# Power_PMIC.net
KiCad netlist of a schematic drawn in Altium Designer
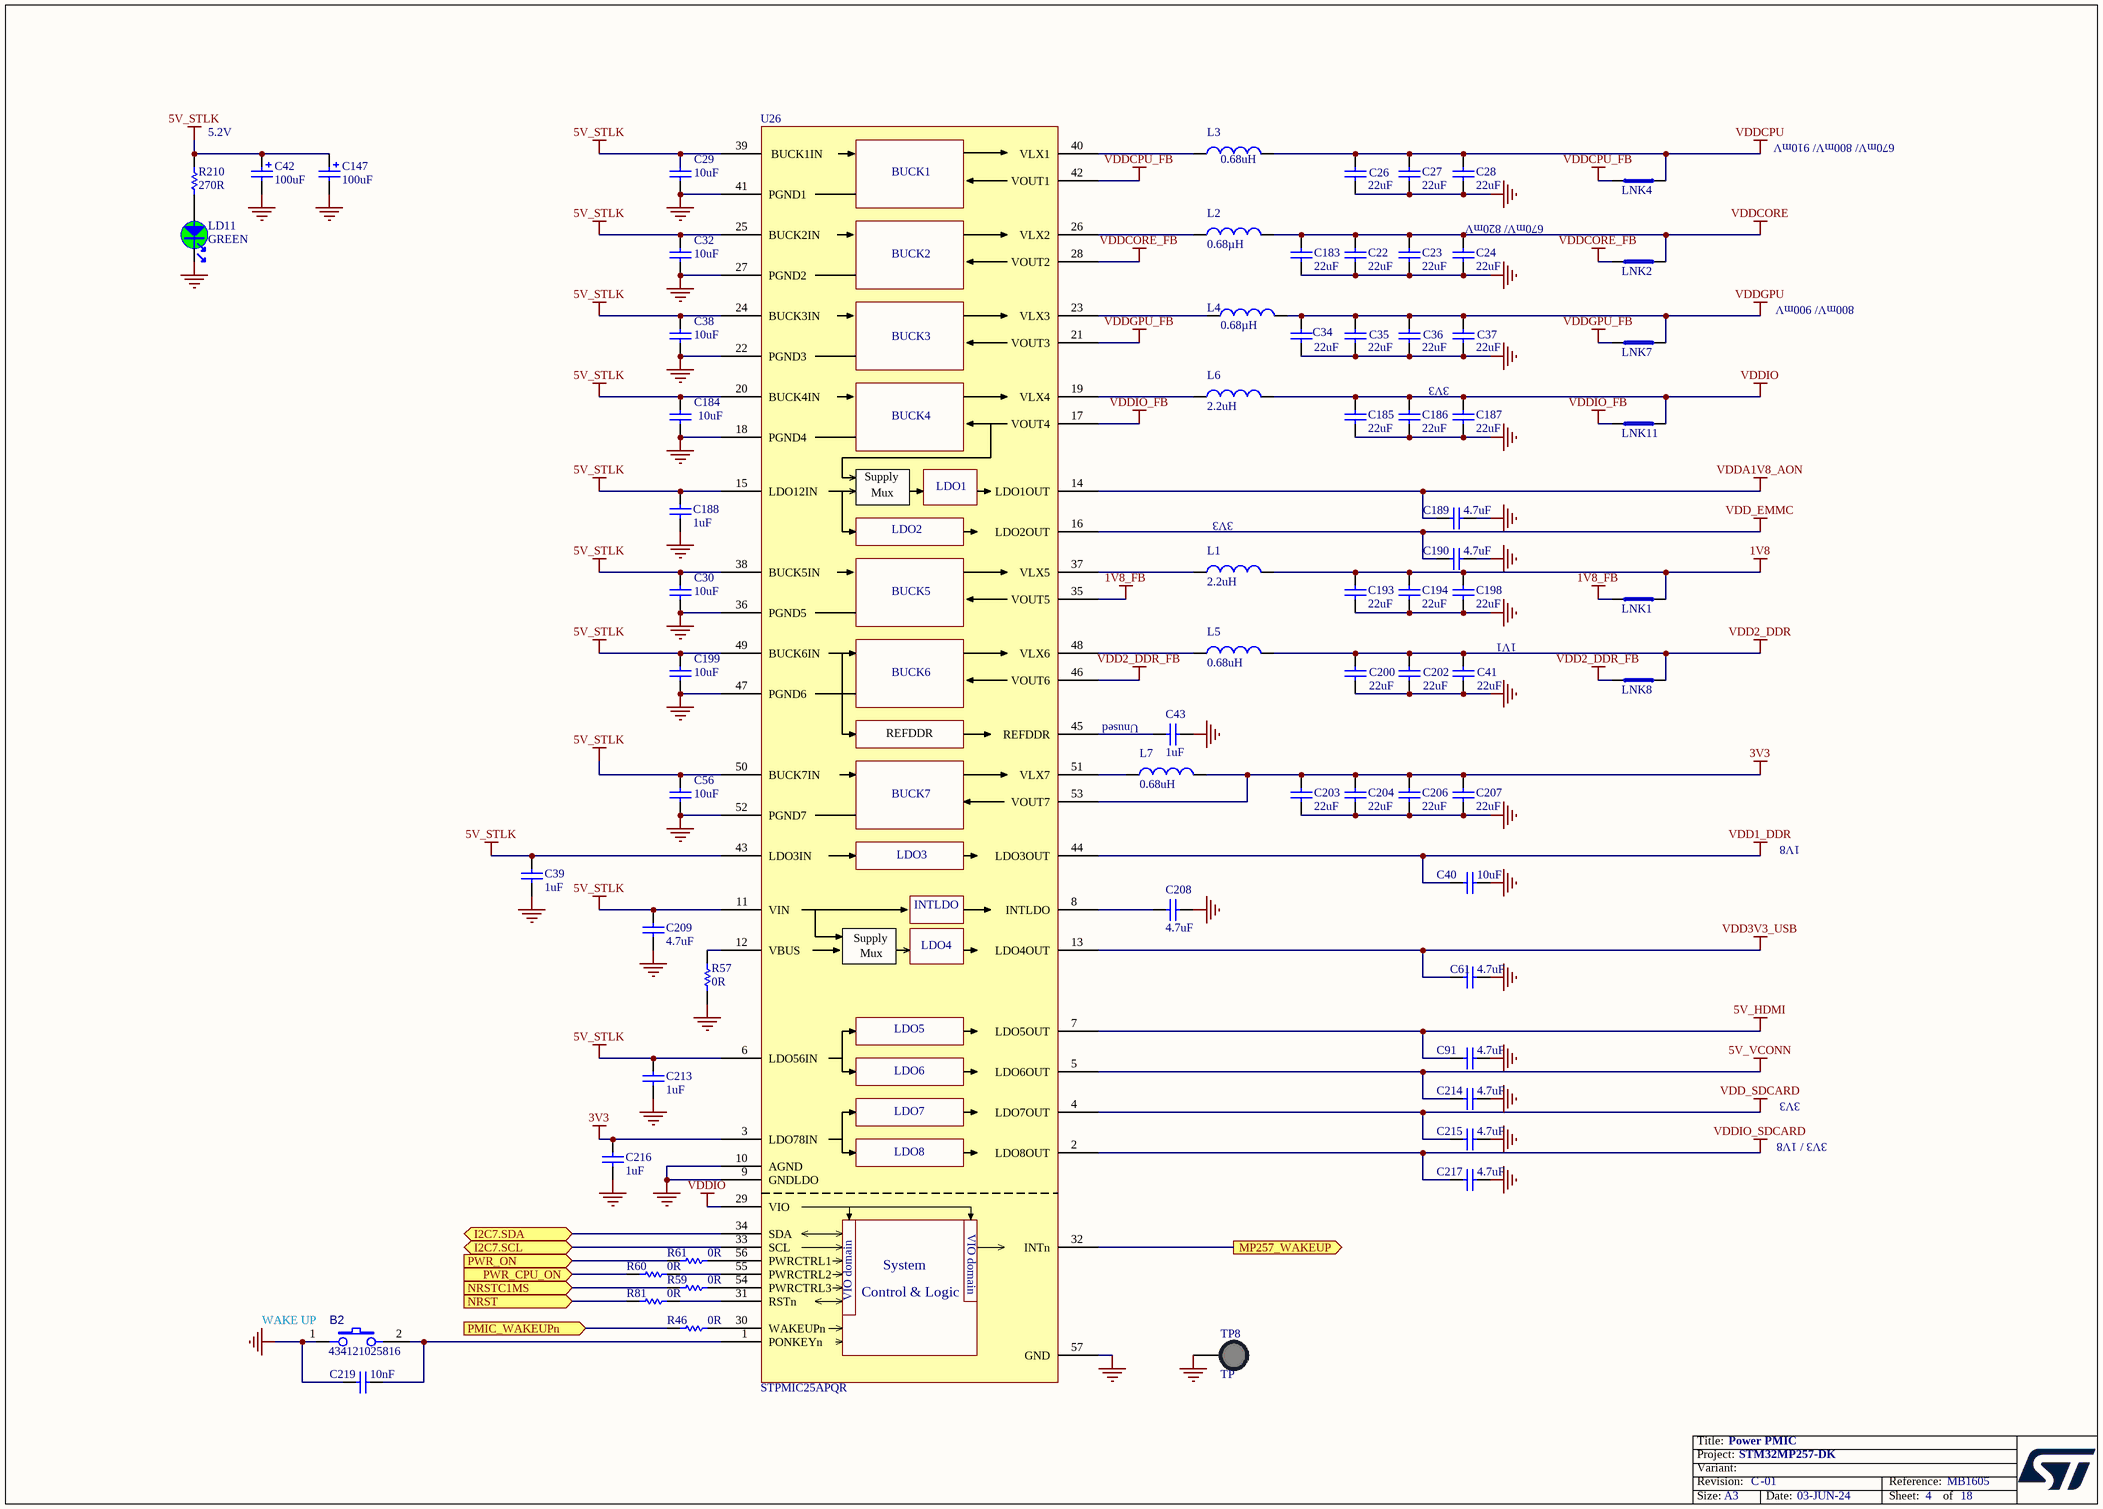
[diagram p0: Power_PMIC.SchDoc]

(export (version "E")
  (design (tool "Eeschema 10.0.6"))
  (components
    (comp (ref "B2")
      (value "434121025816")
      (footprint "SWI_WE_434121025816")
      (description "Switch tactile, SPST-NO, 50mA, 12V, 6x3.8mm")
      (fields
        (field (name "INTERNAL_PART_NUMBER") "MCD-03492")
        (field (name "MANUFACTURER") "WURTH ELEKTRONIC")
      )
      (libsource (lib "MCD_PARTS_database") (part "SW_PUSH_SMD_2P"))
    )
    (comp (ref "C22")
      (value "22uF")
      (footprint "C0603")
      (description "Capacitor, MLCC, 22uF, 6V3, X5R, +/-20%, 0603, T=0,8mm")
      (fields
        (field (name "INTERNAL_PART_NUMBER") "MCD-00100")
        (field (name "MANUFACTURER_PART_NUMBER") "GRM188R60J226MEA0J")
      )
      (libsource (lib "MCD_PARTS_database") (part "Capacitor"))
    )
    (comp (ref "C23")
      (value "22uF")
      (footprint "C0603")
      (description "Capacitor, MLCC, 22uF, 6V3, X5R, +/-20%, 0603, T=0,8mm")
      (fields
        (field (name "INTERNAL_PART_NUMBER") "MCD-00100")
        (field (name "MANUFACTURER_PART_NUMBER") "GRM188R60J226MEA0J")
      )
      (libsource (lib "MCD_PARTS_database") (part "Capacitor"))
    )
    (comp (ref "C24")
      (value "22uF")
      (footprint "C0603")
      (description "Capacitor, MLCC, 22uF, 6V3, X5R, +/-20%, 0603, T=0,8mm")
      (fields
        (field (name "INTERNAL_PART_NUMBER") "MCD-00100")
        (field (name "MANUFACTURER_PART_NUMBER") "GRM188R60J226MEA0J")
      )
      (libsource (lib "MCD_PARTS_database") (part "Capacitor"))
    )
    (comp (ref "C26")
      (value "22uF")
      (footprint "C0603")
      (description "Capacitor, MLCC, 22uF, 6V3, X5R, +/-20%, 0603, T=0,8mm")
      (fields
        (field (name "INTERNAL_PART_NUMBER") "MCD-00100")
        (field (name "MANUFACTURER_PART_NUMBER") "GRM188R60J226MEA0J")
      )
      (libsource (lib "MCD_PARTS_database") (part "Capacitor"))
    )
    (comp (ref "C27")
      (value "22uF")
      (footprint "C0603")
      (description "Capacitor, MLCC, 22uF, 6V3, X5R, +/-20%, 0603, T=0,8mm")
      (fields (field (name "INTERNAL_PART_NUMBER") "MCD-00100") (field (name "MANUFACTURER") "MURATA"))
      (libsource (lib "MCD_PARTS_database") (part "Capacitor"))
    )
    (comp (ref "C28")
      (value "22uF")
      (footprint "C0603")
      (description "Capacitor, MLCC, 22uF, 6V3, X5R, +/-20%, 0603, T=0,8mm")
      (fields (field (name "INTERNAL_PART_NUMBER") "MCD-00100") (field (name "MANUFACTURER") "MURATA"))
      (libsource (lib "MCD_PARTS_database") (part "Capacitor"))
    )
    (comp (ref "C29")
      (value "10uF")
      (footprint "C0603")
      (description "Capacitor, MLCC, 10uF, 10V, X5R, +/-10%, 0603, T=0,8mm")
      (fields
        (field (name "INTERNAL_PART_NUMBER") "MCD-00099")
        (field (name "MANUFACTURER_PART_NUMBER") "GRM188R61A106KE69D")
      )
      (libsource (lib "MCD_PARTS_database") (part "Capacitor"))
    )
    (comp (ref "C30")
      (value "10uF")
      (footprint "C0603")
      (description "Capacitor, MLCC, 10uF, 10V, X5R, +/-10%, 0603, T=0,8mm")
      (fields
        (field (name "INTERNAL_PART_NUMBER") "MCD-00099")
        (field (name "MANUFACTURER_PART_NUMBER") "GRM188R61A106KE69D")
      )
      (libsource (lib "MCD_PARTS_database") (part "Capacitor"))
    )
    (comp (ref "C32")
      (value "10uF")
      (footprint "C0603")
      (description "Capacitor, MLCC, 10uF, 10V, X5R, +/-10%, 0603, T=0,8mm")
      (fields
        (field (name "INTERNAL_PART_NUMBER") "MCD-00099")
        (field (name "MANUFACTURER_PART_NUMBER") "GRM188R61A106KE69D")
      )
      (libsource (lib "MCD_PARTS_database") (part "Capacitor"))
    )
    (comp (ref "C34")
      (value "22uF")
      (footprint "C0603")
      (description "Capacitor, MLCC, 22uF, 6V3, X5R, +/-20%, 0603, T=0,8mm")
      (fields
        (field (name "INTERNAL_PART_NUMBER") "MCD-00100")
        (field (name "MANUFACTURER_PART_NUMBER") "GRM188R60J226MEA0J")
      )
      (libsource (lib "MCD_PARTS_database") (part "Capacitor"))
    )
    (comp (ref "C35")
      (value "22uF")
      (footprint "C0603")
      (description "Capacitor, MLCC, 22uF, 6V3, X5R, +/-20%, 0603, T=0,8mm")
      (fields
        (field (name "INTERNAL_PART_NUMBER") "MCD-00100")
        (field (name "MANUFACTURER_PART_NUMBER") "GRM188R60J226MEA0J")
      )
      (libsource (lib "MCD_PARTS_database") (part "Capacitor"))
    )
    (comp (ref "C36")
      (value "22uF")
      (footprint "C0603")
      (description "Capacitor, MLCC, 22uF, 6V3, X5R, +/-20%, 0603, T=0,8mm")
      (fields
        (field (name "INTERNAL_PART_NUMBER") "MCD-00100")
        (field (name "MANUFACTURER_PART_NUMBER") "GRM188R60J226MEA0J")
      )
      (libsource (lib "MCD_PARTS_database") (part "Capacitor"))
    )
    (comp (ref "C37")
      (value "22uF")
      (footprint "C0603")
      (description "Capacitor, MLCC, 22uF, 6V3, X5R, +/-20%, 0603, T=0,8mm")
      (fields
        (field (name "INTERNAL_PART_NUMBER") "MCD-00100")
        (field (name "MANUFACTURER_PART_NUMBER") "GRM188R60J226MEA0J")
      )
      (libsource (lib "MCD_PARTS_database") (part "Capacitor"))
    )
    (comp (ref "C38")
      (value "10uF")
      (footprint "C0603")
      (description "Capacitor, MLCC, 10uF, 10V, X5R, +/-10%, 0603, T=0,8mm")
      (fields
        (field (name "INTERNAL_PART_NUMBER") "MCD-00099")
        (field (name "MANUFACTURER_PART_NUMBER") "GRM188R61A106KE69D")
      )
      (libsource (lib "MCD_PARTS_database") (part "Capacitor"))
    )
    (comp (ref "C39")
      (value "1uF")
      (footprint "C0402")
      (description "Capacitor, MLCC, 1uF, 25V, X5R, +/-10%, 0402, T=0.5mm")
      (fields (field (name "INTERNAL_PART_NUMBER") "MCD-00095") (field (name "MANUFACTURER") "MURATA"))
      (libsource (lib "MCD_PARTS_database") (part "Capacitor"))
    )
    (comp (ref "C40")
      (value "10uF")
      (footprint "C0402")
      (description "Capacitor, MLCC, 10uF, 6.3V, X5R, +/-20%, 0402, T=0.5mm")
      (fields (field (name "INTERNAL_PART_NUMBER") "MCD-03140") (field (name "MANUFACTURER") "MURATA"))
      (libsource (lib "MCD_PARTS_database") (part "Capacitor"))
    )
    (comp (ref "C41")
      (value "22uF")
      (footprint "C0603")
      (description "Capacitor, MLCC, 22uF, 6V3, X5R, +/-20%, 0603, T=0,8mm")
      (fields
        (field (name "INTERNAL_PART_NUMBER") "MCD-00100")
        (field (name "MANUFACTURER_PART_NUMBER") "GRM188R60J226MEA0J")
      )
      (libsource (lib "MCD_PARTS_database") (part "Capacitor"))
    )
    (comp (ref "C42")
      (value "100uF")
      (footprint "CPOL_TCJ-B_1210_H210")
      (description "Capacitor, Tantalum, 100uF, 6V3, 40mR, +/-20%,  Type_B (3528 metric), T=1.9mm")
      (fields (field (name "INTERNAL_PART_NUMBER") "MCD-01796") (field (name "MANUFACTURER") "AVX"))
      (libsource (lib "MCD_PARTS_database") (part "Cap_POL_TANA"))
    )
    (comp (ref "C43")
      (value "1uF")
      (footprint "C0402")
      (description "Capacitor, MLCC, 1uF, 25V, X5R, +/-10%, 0402, T=0.5mm")
      (fields (field (name "INTERNAL_PART_NUMBER") "MCD-00095") (field (name "MANUFACTURER") "MURATA"))
      (libsource (lib "MCD_PARTS_database") (part "Capacitor"))
    )
    (comp (ref "C56")
      (value "10uF")
      (footprint "C0603")
      (description "Capacitor, MLCC, 10uF, 10V, X5R, +/-10%, 0603, T=0,8mm")
      (fields
        (field (name "INTERNAL_PART_NUMBER") "MCD-00099")
        (field (name "MANUFACTURER_PART_NUMBER") "GRM188R61A106KE69D")
      )
      (libsource (lib "MCD_PARTS_database") (part "Capacitor"))
    )
    (comp (ref "C61")
      (value "4.7uF")
      (footprint "C0402")
      (description "Capacitor, MLCC, 4.7uF, 6V3, X5R, +/-20%, 0402, T=0.5mm")
      (fields
        (field (name "INTERNAL_PART_NUMBER") "MCD-01356")
        (field (name "MANUFACTURER_PART_NUMBER") "GRM155R60J475ME47")
      )
      (libsource (lib "MCD_PARTS_database") (part "Capacitor"))
    )
    (comp (ref "C91")
      (value "4.7uF")
      (footprint "C0402")
      (description "Capacitor, MLCC, 4.7uF, 6V3, X5R, +/-20%, 0402, T=0.5mm")
      (fields
        (field (name "INTERNAL_PART_NUMBER") "MCD-01356")
        (field (name "MANUFACTURER_PART_NUMBER") "GRM155R60J475ME47")
      )
      (libsource (lib "MCD_PARTS_database") (part "Capacitor"))
    )
    (comp (ref "C147")
      (value "100uF")
      (footprint "CPOL_TCJ-B_1210_H210")
      (description "Capacitor, Tantalum, 100uF, 6V3, 40mR, +/-20%,  Type_B (3528 metric), T=1.9mm")
      (fields (field (name "INTERNAL_PART_NUMBER") "MCD-01796") (field (name "MANUFACTURER") "AVX"))
      (libsource (lib "MCD_PARTS_database") (part "Cap_POL_TANA"))
    )
    (comp (ref "C183")
      (value "22uF")
      (footprint "C0603")
      (description "Capacitor, MLCC, 22uF, 6V3, X5R, +/-20%, 0603, T=0,8mm")
      (fields (field (name "INTERNAL_PART_NUMBER") "MCD-00100") (field (name "MANUFACTURER") "MURATA"))
      (libsource (lib "MCD_PARTS_database") (part "Capacitor"))
    )
    (comp (ref "C184")
      (value "10uF")
      (footprint "C0603")
      (description "Capacitor, MLCC, 10uF, 10V, X5R, +/-10%, 0603, T=0,8mm")
      (fields
        (field (name "INTERNAL_PART_NUMBER") "MCD-00099")
        (field (name "MANUFACTURER_PART_NUMBER") "GRM188R61A106KE69D")
      )
      (libsource (lib "MCD_PARTS_database") (part "Capacitor"))
    )
    (comp (ref "C185")
      (value "22uF")
      (footprint "C0805")
      (description "Capacitor, MLCC, 22uF, 10V, X5R, +/-20%, 0805, T=1,25mm")
      (fields (field (name "INTERNAL_PART_NUMBER") "MCD-03139") (field (name "MANUFACTURER") "MURATA"))
      (libsource (lib "MCD_PARTS_database") (part "Capacitor"))
    )
    (comp (ref "C186")
      (value "22uF")
      (footprint "C0805")
      (description "Capacitor, MLCC, 22uF, 10V, X5R, +/-20%, 0805, T=1,25mm")
      (fields (field (name "INTERNAL_PART_NUMBER") "MCD-03139") (field (name "MANUFACTURER") "MURATA"))
      (libsource (lib "MCD_PARTS_database") (part "Capacitor"))
    )
    (comp (ref "C187")
      (value "22uF")
      (footprint "C0805")
      (description "Capacitor, MLCC, 22uF, 10V, X5R, +/-20%, 0805, T=1,25mm")
      (fields (field (name "INTERNAL_PART_NUMBER") "MCD-03139") (field (name "MANUFACTURER") "MURATA"))
      (libsource (lib "MCD_PARTS_database") (part "Capacitor"))
    )
    (comp (ref "C188")
      (value "1uF")
      (footprint "C0402")
      (description "Capacitor, MLCC, 1uF, 25V, X5R, +/-10%, 0402, T=0.5mm")
      (fields (field (name "INTERNAL_PART_NUMBER") "MCD-00095") (field (name "MANUFACTURER") "MURATA"))
      (libsource (lib "MCD_PARTS_database") (part "Capacitor"))
    )
    (comp (ref "C189")
      (value "4.7uF")
      (footprint "C0402")
      (description "Capacitor, MLCC, 4.7uF, 6V3, X5R, +/-20%, 0402, T=0.5mm")
      (fields
        (field (name "INTERNAL_PART_NUMBER") "MCD-01356")
        (field (name "MANUFACTURER_PART_NUMBER") "GRM155R60J475ME47")
      )
      (libsource (lib "MCD_PARTS_database") (part "Capacitor"))
    )
    (comp (ref "C190")
      (value "4.7uF")
      (footprint "C0402")
      (description "Capacitor, MLCC, 4.7uF, 6V3, X5R, +/-20%, 0402, T=0.5mm")
      (fields
        (field (name "INTERNAL_PART_NUMBER") "MCD-01356")
        (field (name "MANUFACTURER_PART_NUMBER") "GRM155R60J475ME47")
      )
      (libsource (lib "MCD_PARTS_database") (part "Capacitor"))
    )
    (comp (ref "C193")
      (value "22uF")
      (footprint "C0805")
      (description "Capacitor, MLCC, 22uF, 10V, X5R, +/-20%, 0805, T=1,25mm")
      (fields (field (name "INTERNAL_PART_NUMBER") "MCD-03139") (field (name "MANUFACTURER") "MURATA"))
      (libsource (lib "MCD_PARTS_database") (part "Capacitor"))
    )
    (comp (ref "C194")
      (value "22uF")
      (footprint "C0805")
      (description "Capacitor, MLCC, 22uF, 10V, X5R, +/-20%, 0805, T=1,25mm")
      (fields (field (name "INTERNAL_PART_NUMBER") "MCD-03139") (field (name "MANUFACTURER") "MURATA"))
      (libsource (lib "MCD_PARTS_database") (part "Capacitor"))
    )
    (comp (ref "C198")
      (value "22uF")
      (footprint "C0805")
      (description "Capacitor, MLCC, 22uF, 10V, X5R, +/-20%, 0805, T=1,25mm")
      (fields (field (name "INTERNAL_PART_NUMBER") "MCD-03139") (field (name "MANUFACTURER") "MURATA"))
      (libsource (lib "MCD_PARTS_database") (part "Capacitor"))
    )
    (comp (ref "C199")
      (value "10uF")
      (footprint "C0603")
      (description "Capacitor, MLCC, 10uF, 10V, X5R, +/-10%, 0603, T=0,8mm")
      (fields
        (field (name "INTERNAL_PART_NUMBER") "MCD-00099")
        (field (name "MANUFACTURER_PART_NUMBER") "GRM188R61A106KE69D")
      )
      (libsource (lib "MCD_PARTS_database") (part "Capacitor"))
    )
    (comp (ref "C200")
      (value "22uF")
      (footprint "C0603")
      (description "Capacitor, MLCC, 22uF, 6V3, X5R, +/-20%, 0603, T=0,8mm")
      (fields
        (field (name "INTERNAL_PART_NUMBER") "MCD-00100")
        (field (name "MANUFACTURER_PART_NUMBER") "GRM188R60J226MEA0J")
      )
      (libsource (lib "MCD_PARTS_database") (part "Capacitor"))
    )
    (comp (ref "C202")
      (value "22uF")
      (footprint "C0603")
      (description "Capacitor, MLCC, 22uF, 6V3, X5R, +/-20%, 0603, T=0,8mm")
      (fields
        (field (name "INTERNAL_PART_NUMBER") "MCD-00100")
        (field (name "MANUFACTURER_PART_NUMBER") "GRM188R60J226MEA0J")
      )
      (libsource (lib "MCD_PARTS_database") (part "Capacitor"))
    )
    (comp (ref "C203")
      (value "22uF")
      (footprint "C0805")
      (description "Capacitor, MLCC, 22uF, 10V, X5R, +/-20%, 0805, T=1,25mm")
      (fields (field (name "INTERNAL_PART_NUMBER") "MCD-03139") (field (name "MANUFACTURER") "MURATA"))
      (libsource (lib "MCD_PARTS_database") (part "Capacitor"))
    )
    (comp (ref "C204")
      (value "22uF")
      (footprint "C0805")
      (description "Capacitor, MLCC, 22uF, 10V, X5R, +/-20%, 0805, T=1,25mm")
      (fields (field (name "INTERNAL_PART_NUMBER") "MCD-03139") (field (name "MANUFACTURER") "MURATA"))
      (libsource (lib "MCD_PARTS_database") (part "Capacitor"))
    )
    (comp (ref "C206")
      (value "22uF")
      (footprint "C0805")
      (description "Capacitor, MLCC, 22uF, 10V, X5R, +/-20%, 0805, T=1,25mm")
      (fields (field (name "INTERNAL_PART_NUMBER") "MCD-03139") (field (name "MANUFACTURER") "MURATA"))
      (libsource (lib "MCD_PARTS_database") (part "Capacitor"))
    )
    (comp (ref "C207")
      (value "22uF")
      (footprint "C0805")
      (description "Capacitor, MLCC, 22uF, 10V, X5R, +/-20%, 0805, T=1,25mm")
      (fields (field (name "INTERNAL_PART_NUMBER") "MCD-03139") (field (name "MANUFACTURER") "MURATA"))
      (libsource (lib "MCD_PARTS_database") (part "Capacitor"))
    )
    (comp (ref "C208")
      (value "4.7uF")
      (footprint "C0402")
      (description "Capacitor, MLCC, 4.7uF, 6V3, X5R, +/-20%, 0402, T=0.5mm")
      (fields
        (field (name "INTERNAL_PART_NUMBER") "MCD-01356")
        (field (name "MANUFACTURER_PART_NUMBER") "GRM155R60J475ME47")
      )
      (libsource (lib "MCD_PARTS_database") (part "Capacitor"))
    )
    (comp (ref "C209")
      (value "4.7uF")
      (footprint "C0402")
      (description "Capacitor, MLCC, 4.7uF, 6V3, X5R, +/-20%, 0402, T=0.5mm")
      (fields
        (field (name "INTERNAL_PART_NUMBER") "MCD-01356")
        (field (name "MANUFACTURER_PART_NUMBER") "GRM155R60J475ME47")
      )
      (libsource (lib "MCD_PARTS_database") (part "Capacitor"))
    )
    (comp (ref "C213")
      (value "1uF")
      (footprint "C0402")
      (description "Capacitor, MLCC, 1uF, 25V, X5R, +/-10%, 0402, T=0.5mm")
      (fields (field (name "INTERNAL_PART_NUMBER") "MCD-00095") (field (name "MANUFACTURER") "MURATA"))
      (libsource (lib "MCD_PARTS_database") (part "Capacitor"))
    )
    (comp (ref "C214")
      (value "4.7uF")
      (footprint "C0402")
      (description "Capacitor, MLCC, 4.7uF, 6V3, X5R, +/-20%, 0402, T=0.5mm")
      (fields
        (field (name "INTERNAL_PART_NUMBER") "MCD-01356")
        (field (name "MANUFACTURER_PART_NUMBER") "GRM155R60J475ME47")
      )
      (libsource (lib "MCD_PARTS_database") (part "Capacitor"))
    )
    (comp (ref "C215")
      (value "4.7uF")
      (footprint "C0402")
      (description "Capacitor, MLCC, 4.7uF, 6V3, X5R, +/-20%, 0402, T=0.5mm")
      (fields
        (field (name "INTERNAL_PART_NUMBER") "MCD-01356")
        (field (name "MANUFACTURER_PART_NUMBER") "GRM155R60J475ME47")
      )
      (libsource (lib "MCD_PARTS_database") (part "Capacitor"))
    )
    (comp (ref "C216")
      (value "1uF")
      (footprint "C0402")
      (description "Capacitor, MLCC, 1uF, 25V, X5R, +/-10%, 0402, T=0.5mm")
      (fields (field (name "INTERNAL_PART_NUMBER") "MCD-00095") (field (name "MANUFACTURER") "MURATA"))
      (libsource (lib "MCD_PARTS_database") (part "Capacitor"))
    )
    (comp (ref "C217")
      (value "4.7uF")
      (footprint "C0402")
      (description "Capacitor, MLCC, 4.7uF, 6V3, X5R, +/-20%, 0402, T=0.5mm")
      (fields
        (field (name "INTERNAL_PART_NUMBER") "MCD-01356")
        (field (name "MANUFACTURER_PART_NUMBER") "GRM155R60J475ME47")
      )
      (libsource (lib "MCD_PARTS_database") (part "Capacitor"))
    )
    (comp (ref "C219")
      (value "10nF")
      (footprint "C0402")
      (description "Capacitor, MLCC, 10nF, 50V, X7R, +/-10%, 0402, T=0.5mm")
      (fields
        (field (name "INTERNAL_PART_NUMBER") "MCD-02198")
        (field (name "MANUFACTURER_PART_NUMBER") "CC0402KRX7R9BB103")
      )
      (libsource (lib "MCD_PARTS_database") (part "Capacitor"))
    )
    (comp (ref "L1")
      (value "2.2uH")
      (footprint "IND_2016_MURATA_LQM2MPN2R2NG0")
      (description "Inductor, 2.2uH, +/-20%, Itemp= 1700mA, Isat= 2400mA, 0R140, 0806, T=1mm")
      (fields (field (name "INTERNAL_PART_NUMBER") "MCD-03143") (field (name "MANUFACTURER") "MURATA"))
      (libsource (lib "MCD_PARTS_database") (part "Inductor"))
    )
    (comp (ref "L2")
      (value "0.68µH")
      (footprint "IND_2520_TOKO_DFE252012P")
      (description "Inductor, 0.68uH, +/-20%, Itemp= 3900mA, Isat= 5400mA, 0R031, 1008, T=1.2mm")
      (fields (field (name "INTERNAL_PART_NUMBER") "MCD-03142") (field (name "MANUFACTURER") "MURATA"))
      (libsource (lib "MCD_PARTS_database") (part "Inductor"))
    )
    (comp (ref "L3")
      (value "0.68uH")
      (footprint "IND_2016_MURATA_LQM2MPN2R2NG0")
      (description "Inductor, 0.68uH, +/-20%, Itemp= 3100mA, Isat= 4300mA, 0R043, 0806, T=1mm")
      (fields (field (name "INTERNAL_PART_NUMBER") "MCD-03141") (field (name "MANUFACTURER") "MURATA"))
      (libsource (lib "MCD_PARTS_database") (part "Inductor"))
    )
    (comp (ref "L4")
      (value "0.68µH")
      (footprint "IND_2520_TOKO_DFE252012P")
      (description "Inductor, 0.68uH, +/-20%, Itemp= 3900mA, Isat= 5400mA, 0R031, 1008, T=1.2mm")
      (fields (field (name "INTERNAL_PART_NUMBER") "MCD-03142") (field (name "MANUFACTURER") "MURATA"))
      (libsource (lib "MCD_PARTS_database") (part "Inductor"))
    )
    (comp (ref "L5")
      (value "0.68uH")
      (footprint "IND_2016_MURATA_LQM2MPN2R2NG0")
      (description "Inductor, 0.68uH, +/-20%, Itemp= 3100mA, Isat= 4300mA, 0R043, 0806, T=1mm")
      (fields (field (name "INTERNAL_PART_NUMBER") "MCD-03141") (field (name "MANUFACTURER") "MURATA"))
      (libsource (lib "MCD_PARTS_database") (part "Inductor"))
    )
    (comp (ref "L6")
      (value "2.2uH")
      (footprint "IND_2016_MURATA_LQM2MPN2R2NG0")
      (description "Inductor, 2.2uH, +/-20%, Itemp= 1700mA, Isat= 2400mA, 0R140, 0806, T=1mm")
      (fields (field (name "INTERNAL_PART_NUMBER") "MCD-03143") (field (name "MANUFACTURER") "MURATA"))
      (libsource (lib "MCD_PARTS_database") (part "Inductor"))
    )
    (comp (ref "L7")
      (value "0.68uH")
      (footprint "IND_2016_MURATA_LQM2MPN2R2NG0")
      (description "Inductor, 0.68uH, +/-20%, Itemp= 3100mA, Isat= 4300mA, 0R043, 0806, T=1mm")
      (fields (field (name "INTERNAL_PART_NUMBER") "MCD-03141") (field (name "MANUFACTURER") "MURATA"))
      (libsource (lib "MCD_PARTS_database") (part "Inductor"))
    )
    (comp (ref "LD11")
      (value "GREEN")
      (footprint "LED_0603_OSRAM_LG-Q396-PS-35_GREEN_1A2K_H0P4")
      (description "LED Green, 0603 SMD, Forward Voltage Typ=2V, Max=2.5V")
      (fields
        (field (name "INTERNAL_PART_NUMBER") "MCD-00588")
        (field (name "MANUFACTURER_PART_NUMBER") "LG Q396-PS-35")
        (field (name "PROVIDED_BY") "SUBCO")
      )
      (libsource (lib "MCD_PARTS_database") (part "LED_green"))
    )
    (comp (ref "LNK1")
      (value "link_200")
      (footprint "LINK200")
      (description "Track link on PCB 200um width for layout routing")
      (fields (field (name "INTERNAL_PART_NUMBER") "MCD-02777"))
      (libsource (lib "MCD_PARTS_database") (part "link_200"))
    )
    (comp (ref "LNK2")
      (value "link_200")
      (footprint "LINK200")
      (description "Track link on PCB 200um width for layout routing")
      (fields (field (name "INTERNAL_PART_NUMBER") "MCD-02777"))
      (libsource (lib "MCD_PARTS_database") (part "link_200"))
    )
    (comp (ref "LNK4")
      (value "link_200")
      (footprint "LINK200")
      (description "Track link on PCB 200um width for layout routing")
      (fields (field (name "INTERNAL_PART_NUMBER") "MCD-02777"))
      (libsource (lib "MCD_PARTS_database") (part "link_200"))
    )
    (comp (ref "LNK7")
      (value "link_200")
      (footprint "LINK200")
      (description "Track link on PCB 200um width for layout routing")
      (fields (field (name "INTERNAL_PART_NUMBER") "MCD-02777"))
      (libsource (lib "MCD_PARTS_database") (part "link_200"))
    )
    (comp (ref "LNK8")
      (value "link_200")
      (footprint "LINK200")
      (description "Track link on PCB 200um width for layout routing")
      (fields (field (name "INTERNAL_PART_NUMBER") "MCD-02777"))
      (libsource (lib "MCD_PARTS_database") (part "link_200"))
    )
    (comp (ref "LNK11")
      (value "link_200")
      (footprint "LINK200")
      (description "Track link on PCB 200um width for layout routing")
      (fields (field (name "INTERNAL_PART_NUMBER") "MCD-02777"))
      (libsource (lib "MCD_PARTS_database") (part "link_200"))
    )
    (comp (ref "R46")
      (value "0R")
      (footprint "R0402")
      (description "Resistor,0R,0402,5%,1/16W")
      (fields
        (field (name "INTERNAL_PART_NUMBER") "MCD-00052")
        (field (name "MANUFACTURER_PART_NUMBER") "RC0402JR-070RL")
        (field (name "PROVIDED_BY") "SUBCO")
      )
      (libsource (lib "MCD_PARTS_database") (part "Resistor"))
    )
    (comp (ref "R57")
      (value "0R")
      (footprint "R0402")
      (description "Resistor,0R,0402,5%,1/16W")
      (fields
        (field (name "INTERNAL_PART_NUMBER") "MCD-00052")
        (field (name "MANUFACTURER_PART_NUMBER") "RC0402JR-070RL")
        (field (name "PROVIDED_BY") "SUBCO")
      )
      (libsource (lib "MCD_PARTS_database") (part "Resistor"))
    )
    (comp (ref "R59")
      (value "0R")
      (footprint "R0402")
      (description "Resistor,0R,0402,5%,1/16W")
      (fields
        (field (name "INTERNAL_PART_NUMBER") "MCD-00052")
        (field (name "MANUFACTURER_PART_NUMBER") "RC0402JR-070RL")
        (field (name "PROVIDED_BY") "SUBCO")
      )
      (libsource (lib "MCD_PARTS_database") (part "Resistor"))
    )
    (comp (ref "R60")
      (value "0R")
      (footprint "R0402")
      (description "Resistor,0R,0402,5%,1/16W")
      (fields
        (field (name "INTERNAL_PART_NUMBER") "MCD-00052")
        (field (name "MANUFACTURER_PART_NUMBER") "RC0402JR-070RL")
        (field (name "PROVIDED_BY") "SUBCO")
      )
      (libsource (lib "MCD_PARTS_database") (part "Resistor"))
    )
    (comp (ref "R61")
      (value "0R")
      (footprint "R0402")
      (description "Resistor,0R,0402,5%,1/16W")
      (fields
        (field (name "INTERNAL_PART_NUMBER") "MCD-00052")
        (field (name "MANUFACTURER_PART_NUMBER") "RC0402JR-070RL")
        (field (name "PROVIDED_BY") "SUBCO")
      )
      (libsource (lib "MCD_PARTS_database") (part "Resistor"))
    )
    (comp (ref "R81")
      (value "0R")
      (footprint "R0402")
      (description "Resistor,0R,0402,5%,1/16W")
      (fields
        (field (name "INTERNAL_PART_NUMBER") "MCD-00052")
        (field (name "MANUFACTURER_PART_NUMBER") "RC0402JR-070RL")
        (field (name "PROVIDED_BY") "SUBCO")
      )
      (libsource (lib "MCD_PARTS_database") (part "Resistor"))
    )
    (comp (ref "R210")
      (value "270R")
      (footprint "R0402")
      (description "Resistor,270R,0402,1%,1/16W")
      (fields
        (field (name "INTERNAL_PART_NUMBER") "MCD-00441")
        (field (name "MANUFACTURER_PART_NUMBER") "RC0402FR-07270RL")
        (field (name "PROVIDED_BY") "SUBCO")
      )
      (libsource (lib "MCD_PARTS_database") (part "Resistor"))
    )
    (comp (ref "TP8")
      (value "TP")
      (footprint "TP_PTH-1P02MM_TEST-TERMINAL_RS_101-2391_BLACK")
      (description "Vero Technologies 1.02mm Black Terminal Post")
      (fields
        (field (name "INTERNAL_PART_NUMBER") "MCD-00713")
        (field (name "MANUFACTURER_PART_NUMBER") "20-2137")
      )
      (libsource (lib "MCD_PARTS_database") (part "Test_pin_conn_black"))
    )
    (comp (ref "U26")
      (value "STPMIC25APQR")
      (footprint "ICC_QFN56-EPAD_6P5X6P5_P040")
      (description "STPMIC2")
      (fields
        (field (name "INTERNAL_PART_NUMBER") "MCD-03000")
        (field (name "MANUFACTURER") "STMICROELECTRONICS")
      )
      (libsource (lib "MCD_PARTS_database") (part "STPMIC2"))
    )
  )
  (nets
    (net (code "1") (name "/I2C7.SCL") (class "Default")
      (node (ref "U26") (pin "33") (pinfunction "SCL_33") (pintype "passive"))
    )
    (net (code "2") (name "/I2C7.SDA") (class "Default")
      (node (ref "U26") (pin "34") (pinfunction "SDA_34") (pintype "passive"))
    )
    (net (code "3") (name "/MP257_WAKEUP") (class "Default")
      (node (ref "U26") (pin "32") (pinfunction "INTn_32") (pintype "passive"))
    )
    (net (code "4") (name "/NRST") (class "Default")
      (node (ref "R81") (pin "1") (pinfunction "1_1") (pintype "passive"))
    )
    (net (code "5") (name "/NRSTC1MS") (class "Default")
      (node (ref "R59") (pin "1") (pinfunction "1_1") (pintype "passive"))
    )
    (net (code "6") (name "/PMIC_WAKEUPn") (class "Default")
      (node (ref "R46") (pin "1") (pinfunction "1_1") (pintype "passive"))
    )
    (net (code "7") (name "/PWR_CPU_ON") (class "Default")
      (node (ref "R60") (pin "1") (pinfunction "1_1") (pintype "passive"))
    )
    (net (code "8") (name "/PWR_ON") (class "Default")
      (node (ref "R61") (pin "1") (pinfunction "1_1") (pintype "passive"))
    )
    (net (code "9") (name "1V8") (class "Default")
      (node (ref "C193") (pin "2") (pinfunction "2_2") (pintype "passive"))
      (node (ref "C194") (pin "2") (pinfunction "2_2") (pintype "passive"))
      (node (ref "C198") (pin "2") (pinfunction "2_2") (pintype "passive"))
      (node (ref "L1") (pin "2") (pinfunction "2_2") (pintype "passive"))
      (node (ref "LNK1") (pin "2") (pinfunction "2_2") (pintype "passive"))
    )
    (net (code "10") (name "1V8_FB") (class "Default")
      (node (ref "LNK1") (pin "1") (pinfunction "1_1") (pintype "passive"))
      (node (ref "U26") (pin "35") (pinfunction "VOUT5_35") (pintype "passive"))
    )
    (net (code "11") (name "3V3") (class "Default")
      (node (ref "C203") (pin "2") (pinfunction "2_2") (pintype "passive"))
      (node (ref "C204") (pin "2") (pinfunction "2_2") (pintype "passive"))
      (node (ref "C206") (pin "2") (pinfunction "2_2") (pintype "passive"))
      (node (ref "C207") (pin "2") (pinfunction "2_2") (pintype "passive"))
      (node (ref "C216") (pin "2") (pinfunction "2_2") (pintype "passive"))
      (node (ref "L7") (pin "2") (pinfunction "2_2") (pintype "passive"))
      (node (ref "U26") (pin "3") (pinfunction "LDO78IN_3") (pintype "passive"))
      (node (ref "U26") (pin "53") (pinfunction "VOUT7_53") (pintype "passive"))
    )
    (net (code "12") (name "5V_HDMI") (class "Default")
      (node (ref "C91") (pin "1") (pinfunction "1_1") (pintype "passive"))
      (node (ref "U26") (pin "7") (pinfunction "LDO5OUT_7") (pintype "passive"))
    )
    (net (code "13") (name "5V_STLK") (class "Default")
      (node (ref "C147") (pin "1") (pinfunction "1_1") (pintype "passive"))
      (node (ref "C184") (pin "2") (pinfunction "2_2") (pintype "passive"))
      (node (ref "C188") (pin "2") (pinfunction "2_2") (pintype "passive"))
      (node (ref "C199") (pin "2") (pinfunction "2_2") (pintype "passive"))
      (node (ref "C209") (pin "2") (pinfunction "2_2") (pintype "passive"))
      (node (ref "C213") (pin "2") (pinfunction "2_2") (pintype "passive"))
      (node (ref "C29") (pin "2") (pinfunction "2_2") (pintype "passive"))
      (node (ref "C30") (pin "2") (pinfunction "2_2") (pintype "passive"))
      (node (ref "C32") (pin "2") (pinfunction "2_2") (pintype "passive"))
      (node (ref "C38") (pin "2") (pinfunction "2_2") (pintype "passive"))
      (node (ref "C39") (pin "2") (pinfunction "2_2") (pintype "passive"))
      (node (ref "C42") (pin "1") (pinfunction "1_1") (pintype "passive"))
      (node (ref "C56") (pin "2") (pinfunction "2_2") (pintype "passive"))
      (node (ref "R210") (pin "1") (pinfunction "1_1") (pintype "passive"))
      (node (ref "U26") (pin "11") (pinfunction "VIN_11") (pintype "passive"))
      (node (ref "U26") (pin "15") (pinfunction "LDO12IN_15") (pintype "passive"))
      (node (ref "U26") (pin "20") (pinfunction "BUCK4IN_20") (pintype "passive"))
      (node (ref "U26") (pin "24") (pinfunction "BUCK3IN_24") (pintype "passive"))
      (node (ref "U26") (pin "25") (pinfunction "BUCK2IN_25") (pintype "passive"))
      (node (ref "U26") (pin "38") (pinfunction "BUCK5IN_38") (pintype "passive"))
      (node (ref "U26") (pin "39") (pinfunction "BUCK1IN_39") (pintype "passive"))
      (node (ref "U26") (pin "43") (pinfunction "LDO3IN_43") (pintype "passive"))
      (node (ref "U26") (pin "49") (pinfunction "BUCK6IN_49") (pintype "passive"))
      (node (ref "U26") (pin "50") (pinfunction "BUCK7IN_50") (pintype "passive"))
      (node (ref "U26") (pin "6") (pinfunction "LDO56IN_6") (pintype "passive"))
    )
    (net (code "14") (name "5V_VCONN") (class "Default")
      (node (ref "C214") (pin "1") (pinfunction "1_1") (pintype "passive"))
      (node (ref "U26") (pin "5") (pinfunction "LDO6OUT_5") (pintype "passive"))
    )
    (net (code "15") (name "GND") (class "Default")
      (node (ref "B2") (pin "1") (pinfunction "1_1") (pintype "passive"))
      (node (ref "C147") (pin "2") (pinfunction "2_2") (pintype "passive"))
      (node (ref "C183") (pin "1") (pinfunction "1_1") (pintype "passive"))
      (node (ref "C184") (pin "1") (pinfunction "1_1") (pintype "passive"))
      (node (ref "C185") (pin "1") (pinfunction "1_1") (pintype "passive"))
      (node (ref "C186") (pin "1") (pinfunction "1_1") (pintype "passive"))
      (node (ref "C187") (pin "1") (pinfunction "1_1") (pintype "passive"))
      (node (ref "C188") (pin "1") (pinfunction "1_1") (pintype "passive"))
      (node (ref "C189") (pin "1") (pinfunction "1_1") (pintype "passive"))
      (node (ref "C190") (pin "2") (pinfunction "2_2") (pintype "passive"))
      (node (ref "C193") (pin "1") (pinfunction "1_1") (pintype "passive"))
      (node (ref "C194") (pin "1") (pinfunction "1_1") (pintype "passive"))
      (node (ref "C198") (pin "1") (pinfunction "1_1") (pintype "passive"))
      (node (ref "C199") (pin "1") (pinfunction "1_1") (pintype "passive"))
      (node (ref "C200") (pin "1") (pinfunction "1_1") (pintype "passive"))
      (node (ref "C202") (pin "1") (pinfunction "1_1") (pintype "passive"))
      (node (ref "C203") (pin "1") (pinfunction "1_1") (pintype "passive"))
      (node (ref "C204") (pin "1") (pinfunction "1_1") (pintype "passive"))
      (node (ref "C206") (pin "1") (pinfunction "1_1") (pintype "passive"))
      (node (ref "C207") (pin "1") (pinfunction "1_1") (pintype "passive"))
      (node (ref "C208") (pin "2") (pinfunction "2_2") (pintype "passive"))
      (node (ref "C209") (pin "1") (pinfunction "1_1") (pintype "passive"))
      (node (ref "C213") (pin "1") (pinfunction "1_1") (pintype "passive"))
      (node (ref "C214") (pin "2") (pinfunction "2_2") (pintype "passive"))
      (node (ref "C215") (pin "2") (pinfunction "2_2") (pintype "passive"))
      (node (ref "C216") (pin "1") (pinfunction "1_1") (pintype "passive"))
      (node (ref "C217") (pin "2") (pinfunction "2_2") (pintype "passive"))
      (node (ref "C219") (pin "1") (pinfunction "1_1") (pintype "passive"))
      (node (ref "C22") (pin "1") (pinfunction "1_1") (pintype "passive"))
      (node (ref "C23") (pin "1") (pinfunction "1_1") (pintype "passive"))
      (node (ref "C24") (pin "1") (pinfunction "1_1") (pintype "passive"))
      (node (ref "C26") (pin "1") (pinfunction "1_1") (pintype "passive"))
      (node (ref "C27") (pin "1") (pinfunction "1_1") (pintype "passive"))
      (node (ref "C28") (pin "1") (pinfunction "1_1") (pintype "passive"))
      (node (ref "C29") (pin "1") (pinfunction "1_1") (pintype "passive"))
      (node (ref "C30") (pin "1") (pinfunction "1_1") (pintype "passive"))
      (node (ref "C32") (pin "1") (pinfunction "1_1") (pintype "passive"))
      (node (ref "C34") (pin "1") (pinfunction "1_1") (pintype "passive"))
      (node (ref "C35") (pin "1") (pinfunction "1_1") (pintype "passive"))
      (node (ref "C36") (pin "1") (pinfunction "1_1") (pintype "passive"))
      (node (ref "C37") (pin "1") (pinfunction "1_1") (pintype "passive"))
      (node (ref "C38") (pin "1") (pinfunction "1_1") (pintype "passive"))
      (node (ref "C39") (pin "1") (pinfunction "1_1") (pintype "passive"))
      (node (ref "C40") (pin "1") (pinfunction "1_1") (pintype "passive"))
      (node (ref "C41") (pin "1") (pinfunction "1_1") (pintype "passive"))
      (node (ref "C42") (pin "2") (pinfunction "2_2") (pintype "passive"))
      (node (ref "C43") (pin "1") (pinfunction "1_1") (pintype "passive"))
      (node (ref "C56") (pin "1") (pinfunction "1_1") (pintype "passive"))
      (node (ref "C61") (pin "1") (pinfunction "1_1") (pintype "passive"))
      (node (ref "C91") (pin "2") (pinfunction "2_2") (pintype "passive"))
      (node (ref "LD11") (pin "2") (pintype "passive"))
      (node (ref "R57") (pin "1") (pinfunction "1_1") (pintype "passive"))
      (node (ref "TP8") (pin "1") (pinfunction "1_1") (pintype "passive"))
      (node (ref "U26") (pin "10") (pinfunction "AGND_10") (pintype "passive"))
      (node (ref "U26") (pin "18") (pinfunction "PGND4_18") (pintype "passive"))
      (node (ref "U26") (pin "22") (pinfunction "PGND3_22") (pintype "passive"))
      (node (ref "U26") (pin "27") (pinfunction "PGND2_27") (pintype "passive"))
      (node (ref "U26") (pin "36") (pinfunction "PGND5_36") (pintype "passive"))
      (node (ref "U26") (pin "41") (pinfunction "PGND1_41") (pintype "passive"))
      (node (ref "U26") (pin "47") (pinfunction "PGND6_47") (pintype "passive"))
      (node (ref "U26") (pin "52") (pinfunction "PGND7_52") (pintype "passive"))
      (node (ref "U26") (pin "57") (pinfunction "GND_57") (pintype "passive"))
      (node (ref "U26") (pin "9") (pinfunction "GNDLDO_9") (pintype "passive"))
    )
    (net (code "16") (name "Net-(LD11-Pad1)") (class "Default")
      (node (ref "LD11") (pin "1") (pintype "passive"))
      (node (ref "R210") (pin "2") (pinfunction "2_2") (pintype "passive"))
    )
    (net (code "17") (name "Net-(U26-INTLDO)") (class "Default")
      (node (ref "C208") (pin "1") (pinfunction "1_1") (pintype "passive"))
      (node (ref "U26") (pin "8") (pinfunction "INTLDO_8") (pintype "passive"))
    )
    (net (code "18") (name "Net-(U26-PONKEYn)") (class "Default")
      (node (ref "B2") (pin "2") (pinfunction "2_2") (pintype "passive"))
      (node (ref "C219") (pin "2") (pinfunction "2_2") (pintype "passive"))
      (node (ref "U26") (pin "1") (pinfunction "PONKEYn_1") (pintype "passive"))
    )
    (net (code "19") (name "Net-(U26-PWRCTRL1)") (class "Default")
      (node (ref "R61") (pin "2") (pinfunction "2_2") (pintype "passive"))
      (node (ref "U26") (pin "56") (pinfunction "PWRCTRL1_56") (pintype "passive"))
    )
    (net (code "20") (name "Net-(U26-PWRCTRL2)") (class "Default")
      (node (ref "R60") (pin "2") (pinfunction "2_2") (pintype "passive"))
      (node (ref "U26") (pin "55") (pinfunction "PWRCTRL2_55") (pintype "passive"))
    )
    (net (code "21") (name "Net-(U26-PWRCTRL3)") (class "Default")
      (node (ref "R59") (pin "2") (pinfunction "2_2") (pintype "passive"))
      (node (ref "U26") (pin "54") (pinfunction "PWRCTRL3_54") (pintype "passive"))
    )
    (net (code "22") (name "Net-(U26-REFDDR)") (class "Default")
      (node (ref "C43") (pin "2") (pinfunction "2_2") (pintype "passive"))
      (node (ref "U26") (pin "45") (pinfunction "REFDDR_45") (pintype "passive"))
    )
    (net (code "23") (name "Net-(U26-RSTn)") (class "Default")
      (node (ref "R81") (pin "2") (pinfunction "2_2") (pintype "passive"))
      (node (ref "U26") (pin "31") (pinfunction "RSTn_31") (pintype "passive"))
    )
    (net (code "24") (name "Net-(U26-VBUS)") (class "Default")
      (node (ref "R57") (pin "2") (pinfunction "2_2") (pintype "passive"))
      (node (ref "U26") (pin "12") (pinfunction "VBUS_12") (pintype "passive"))
    )
    (net (code "25") (name "Net-(U26-VLX1)") (class "Default")
      (node (ref "L3") (pin "1") (pinfunction "1_1") (pintype "passive"))
      (node (ref "U26") (pin "40") (pinfunction "VLX1_40") (pintype "passive"))
    )
    (net (code "26") (name "Net-(U26-VLX2)") (class "Default")
      (node (ref "L2") (pin "1") (pinfunction "1_1") (pintype "passive"))
      (node (ref "U26") (pin "26") (pinfunction "VLX2_26") (pintype "passive"))
    )
    (net (code "27") (name "Net-(U26-VLX3)") (class "Default")
      (node (ref "L4") (pin "1") (pinfunction "1_1") (pintype "passive"))
      (node (ref "U26") (pin "23") (pinfunction "VLX3_23") (pintype "passive"))
    )
    (net (code "28") (name "Net-(U26-VLX4)") (class "Default")
      (node (ref "L6") (pin "1") (pinfunction "1_1") (pintype "passive"))
      (node (ref "U26") (pin "19") (pinfunction "VLX4_19") (pintype "passive"))
    )
    (net (code "29") (name "Net-(U26-VLX5)") (class "Default")
      (node (ref "L1") (pin "1") (pinfunction "1_1") (pintype "passive"))
      (node (ref "U26") (pin "37") (pinfunction "VLX5_37") (pintype "passive"))
    )
    (net (code "30") (name "Net-(U26-VLX6)") (class "Default")
      (node (ref "L5") (pin "1") (pinfunction "1_1") (pintype "passive"))
      (node (ref "U26") (pin "48") (pinfunction "VLX6_48") (pintype "passive"))
    )
    (net (code "31") (name "Net-(U26-VLX7)") (class "Default")
      (node (ref "L7") (pin "1") (pinfunction "1_1") (pintype "passive"))
      (node (ref "U26") (pin "51") (pinfunction "VLX7_51") (pintype "passive"))
    )
    (net (code "32") (name "Net-(U26-WAKEUPn)") (class "Default")
      (node (ref "R46") (pin "2") (pinfunction "2_2") (pintype "passive"))
      (node (ref "U26") (pin "30") (pinfunction "WAKEUPn_30") (pintype "passive"))
    )
    (net (code "33") (name "VDD1_DDR") (class "Default")
      (node (ref "C40") (pin "2") (pinfunction "2_2") (pintype "passive"))
      (node (ref "U26") (pin "44") (pinfunction "LDO3OUT_44") (pintype "passive"))
    )
    (net (code "34") (name "VDD2_DDR") (class "Default")
      (node (ref "C200") (pin "2") (pinfunction "2_2") (pintype "passive"))
      (node (ref "C202") (pin "2") (pinfunction "2_2") (pintype "passive"))
      (node (ref "C41") (pin "2") (pinfunction "2_2") (pintype "passive"))
      (node (ref "L5") (pin "2") (pinfunction "2_2") (pintype "passive"))
      (node (ref "LNK8") (pin "2") (pinfunction "2_2") (pintype "passive"))
    )
    (net (code "35") (name "VDD2_DDR_FB") (class "Default")
      (node (ref "LNK8") (pin "1") (pinfunction "1_1") (pintype "passive"))
      (node (ref "U26") (pin "46") (pinfunction "VOUT6_46") (pintype "passive"))
    )
    (net (code "36") (name "VDD3V3_USB") (class "Default")
      (node (ref "C61") (pin "2") (pinfunction "2_2") (pintype "passive"))
      (node (ref "U26") (pin "13") (pinfunction "LDO4OUT_13") (pintype "passive"))
    )
    (net (code "37") (name "VDDA1V8_AON") (class "Default")
      (node (ref "C189") (pin "2") (pinfunction "2_2") (pintype "passive"))
      (node (ref "U26") (pin "14") (pinfunction "LDO1OUT_14") (pintype "passive"))
    )
    (net (code "38") (name "VDDCORE") (class "Default")
      (node (ref "C183") (pin "2") (pinfunction "2_2") (pintype "passive"))
      (node (ref "C22") (pin "2") (pinfunction "2_2") (pintype "passive"))
      (node (ref "C23") (pin "2") (pinfunction "2_2") (pintype "passive"))
      (node (ref "C24") (pin "2") (pinfunction "2_2") (pintype "passive"))
      (node (ref "L2") (pin "2") (pinfunction "2_2") (pintype "passive"))
      (node (ref "LNK2") (pin "2") (pinfunction "2_2") (pintype "passive"))
    )
    (net (code "39") (name "VDDCORE_FB") (class "Default")
      (node (ref "LNK2") (pin "1") (pinfunction "1_1") (pintype "passive"))
      (node (ref "U26") (pin "28") (pinfunction "VOUT2_28") (pintype "passive"))
    )
    (net (code "40") (name "VDDCPU") (class "Default")
      (node (ref "C26") (pin "2") (pinfunction "2_2") (pintype "passive"))
      (node (ref "C27") (pin "2") (pinfunction "2_2") (pintype "passive"))
      (node (ref "C28") (pin "2") (pinfunction "2_2") (pintype "passive"))
      (node (ref "L3") (pin "2") (pinfunction "2_2") (pintype "passive"))
      (node (ref "LNK4") (pin "1") (pinfunction "1_1") (pintype "passive"))
    )
    (net (code "41") (name "VDDCPU_FB") (class "Default")
      (node (ref "LNK4") (pin "2") (pinfunction "2_2") (pintype "passive"))
      (node (ref "U26") (pin "42") (pinfunction "VOUT1_42") (pintype "passive"))
    )
    (net (code "42") (name "VDDGPU") (class "Default")
      (node (ref "C34") (pin "2") (pinfunction "2_2") (pintype "passive"))
      (node (ref "C35") (pin "2") (pinfunction "2_2") (pintype "passive"))
      (node (ref "C36") (pin "2") (pinfunction "2_2") (pintype "passive"))
      (node (ref "C37") (pin "2") (pinfunction "2_2") (pintype "passive"))
      (node (ref "L4") (pin "2") (pinfunction "2_2") (pintype "passive"))
      (node (ref "LNK7") (pin "2") (pinfunction "2_2") (pintype "passive"))
    )
    (net (code "43") (name "VDDGPU_FB") (class "Default")
      (node (ref "LNK7") (pin "1") (pinfunction "1_1") (pintype "passive"))
      (node (ref "U26") (pin "21") (pinfunction "VOUT3_21") (pintype "passive"))
    )
    (net (code "44") (name "VDDIO") (class "Default")
      (node (ref "C185") (pin "2") (pinfunction "2_2") (pintype "passive"))
      (node (ref "C186") (pin "2") (pinfunction "2_2") (pintype "passive"))
      (node (ref "C187") (pin "2") (pinfunction "2_2") (pintype "passive"))
      (node (ref "L6") (pin "2") (pinfunction "2_2") (pintype "passive"))
      (node (ref "LNK11") (pin "2") (pinfunction "2_2") (pintype "passive"))
      (node (ref "U26") (pin "29") (pinfunction "VIO_29") (pintype "passive"))
    )
    (net (code "45") (name "VDDIO_FB") (class "Default")
      (node (ref "LNK11") (pin "1") (pinfunction "1_1") (pintype "passive"))
      (node (ref "U26") (pin "17") (pinfunction "VOUT4_17") (pintype "passive"))
    )
    (net (code "46") (name "VDDIO_SDCARD") (class "Default")
      (node (ref "C217") (pin "1") (pinfunction "1_1") (pintype "passive"))
      (node (ref "U26") (pin "2") (pinfunction "LDO8OUT_2") (pintype "passive"))
    )
    (net (code "47") (name "VDD_EMMC") (class "Default")
      (node (ref "C190") (pin "1") (pinfunction "1_1") (pintype "passive"))
      (node (ref "U26") (pin "16") (pinfunction "LDO2OUT_16") (pintype "passive"))
    )
    (net (code "48") (name "VDD_SDCARD") (class "Default")
      (node (ref "C215") (pin "1") (pinfunction "1_1") (pintype "passive"))
      (node (ref "U26") (pin "4") (pinfunction "LDO7OUT_4") (pintype "passive"))
    )
  )
)
